# Smoothing_shematic_2022-05-04.net
KiCad netlist of a schematic drawn in Altium Designer
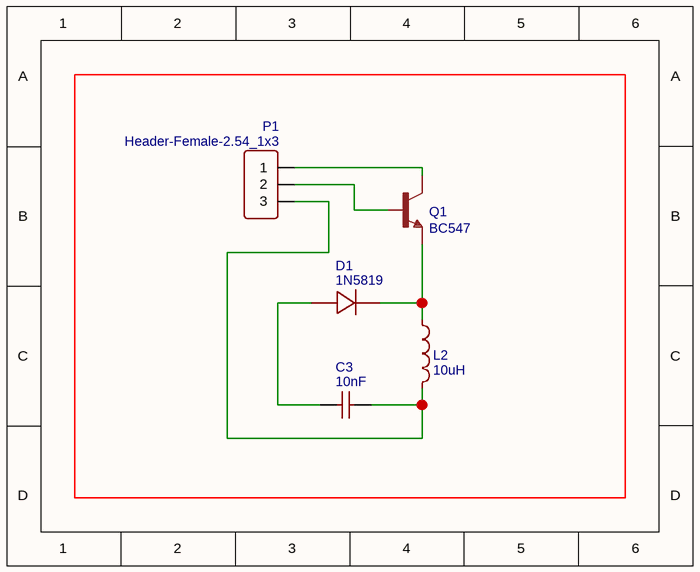
[diagram p0: Smoothing_shematic_2022-05-04.schdoc]

(export (version "E")
  (design (tool "Eeschema 10.0.6"))
  (components
    (comp (ref "C3")
      (value "10nF")
      (fields
        (field (name "BOM_MANUFACTURER PART") "22pf/50V 10%")
        (field (name "BOM_SUPPLIER PART") "C9316")
      )
      (libsource (lib "altium-import") (part "root_0_10nF_"))
    )
    (comp (ref "D1")
      (value "1N5819")
      (fields (field (name "BOM_SUPPLIER PART") "C256527") (field (name "CONTRIBUTOR") "LCSC"))
      (libsource (lib "altium-import") (part "root_2_1N5819_"))
    )
    (comp (ref "L2")
      (value "10uH")
      (fields
        (field (name "BOM_MANUFACTURER PART") "General Inductor(TH)/10uH电感")
        (field (name "BOM_SUPPLIER PART") "C27938")
      )
      (libsource (lib "altium-import") (part "root_3_10uH_"))
    )
    (comp (ref "P1")
      (value "Header-Female-2.54_1x3")
      (fields (field (name "BOM_SUPPLIER PART") "C146243"))
      (libsource (lib "altium-import") (part "root_0_Header-Female-2.54_1x3_"))
    )
    (comp (ref "Q1")
      (value "BC547")
      (description "Generic NPN BJT")
      (fields (field (name "BOM_MANUFACTURER PART") "?") (field (name "CONTRIBUTOR") "SparkFun"))
      (libsource (lib "altium-import") (part "root_0_BC547_"))
    )
  )
  (nets
    (net (code "1") (name "Net-(C3-Pad2)") (class "Default")
      (node (ref "C3") (pin "2") (pinfunction "2_2") (pintype "passive"))
      (node (ref "L2") (pin "2") (pinfunction "2_2") (pintype "passive"))
      (node (ref "P1") (pin "3") (pinfunction "3_3") (pintype "passive"))
    )
    (net (code "2") (name "Net-(D1-A)") (class "Default")
      (node (ref "C3") (pin "1") (pinfunction "1_1") (pintype "passive"))
      (node (ref "D1") (pin "2") (pinfunction "A_2") (pintype "passive"))
    )
    (net (code "3") (name "Net-(D1-K)") (class "Default")
      (node (ref "D1") (pin "1") (pinfunction "K_1") (pintype "passive"))
      (node (ref "L2") (pin "1") (pinfunction "1_1") (pintype "passive"))
      (node (ref "Q1") (pin "3") (pinfunction "E_3") (pintype "passive"))
    )
    (net (code "4") (name "Net-(Q1-B)") (class "Default")
      (node (ref "P1") (pin "2") (pinfunction "2_2") (pintype "passive"))
      (node (ref "Q1") (pin "2") (pinfunction "B_2") (pintype "passive"))
    )
    (net (code "5") (name "Net-(Q1-C)") (class "Default")
      (node (ref "P1") (pin "1") (pinfunction "1_1") (pintype "passive"))
      (node (ref "Q1") (pin "1") (pinfunction "C_1") (pintype "passive"))
    )
  )
)
